# Towtank_manual_direction.net
KiCad netlist of a schematic drawn in EAGLE
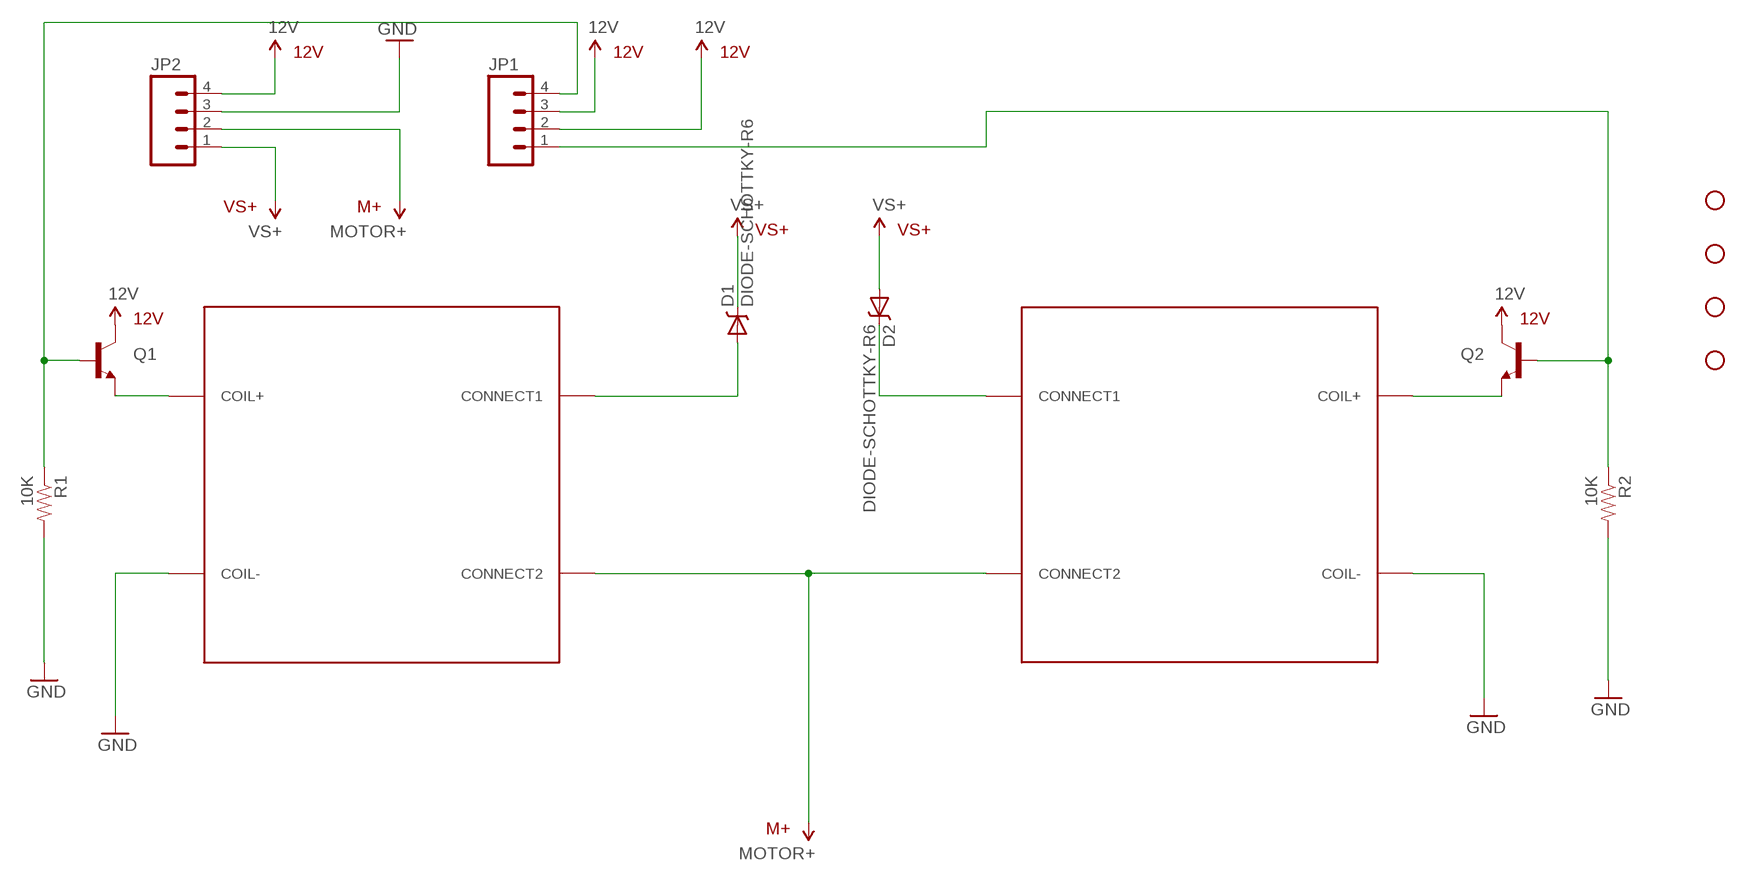
[diagram p0: schematic, sheet 1]

(export (version "E")
  (design (tool "Eeschema 10.0.6"))
  (components
    (comp (ref "D1")
      (value "DIODE-SCHOTTKY-R6")
      (footprint "eagle-import:R6-AXIAL")
      (libsource (lib "eagle-import") (part "DIODE-SCHOTTKY-R6"))
    )
    (comp (ref "D2")
      (value "DIODE-SCHOTTKY-R6")
      (footprint "eagle-import:R6-AXIAL")
      (libsource (lib "eagle-import") (part "DIODE-SCHOTTKY-R6"))
    )
    (comp (ref "JP1")
      (value "M04LOCK_LONGPADS")
      (footprint "eagle-import:1X04_LOCK_LONGPADS")
      (libsource (lib "eagle-import") (part "M04LOCK_LONGPADS"))
    )
    (comp (ref "JP2")
      (value "M04SCREW_LOCK")
      (footprint "eagle-import:SCREWTERMINAL-3.5MM-4_LOCK")
      (libsource (lib "eagle-import") (part "M04SCREW_LOCK"))
    )
    (comp (ref "JP3")
      (value "STAND-OFF")
      (footprint "eagle-import:STAND-OFF")
      (libsource (lib "eagle-import") (part "STAND-OFF"))
    )
    (comp (ref "JP4")
      (value "STAND-OFF")
      (footprint "eagle-import:STAND-OFF")
      (libsource (lib "eagle-import") (part "STAND-OFF"))
    )
    (comp (ref "JP5")
      (value "STAND-OFF")
      (footprint "eagle-import:STAND-OFF")
      (libsource (lib "eagle-import") (part "STAND-OFF"))
    )
    (comp (ref "JP6")
      (value "STAND-OFF")
      (footprint "eagle-import:STAND-OFF")
      (libsource (lib "eagle-import") (part "STAND-OFF"))
    )
    (comp (ref "Q1")
      (value "TRANSISTOR_NPNTO-92-AMMO")
      (footprint "eagle-import:TO-92-AMMO")
      (libsource (lib "eagle-import") (part "TRANSISTOR_NPNTO-92-AMMO"))
    )
    (comp (ref "Q2")
      (value "TRANSISTOR_NPNTO-92-AMMO")
      (footprint "eagle-import:TO-92-AMMO")
      (libsource (lib "eagle-import") (part "TRANSISTOR_NPNTO-92-AMMO"))
    )
    (comp (ref "R1")
      (value "10K")
      (footprint "eagle-import:AXIAL-0.4")
      (libsource (lib "eagle-import") (part "RESISTORPTH-1/4W"))
    )
    (comp (ref "R2")
      (value "10K")
      (footprint "eagle-import:AXIAL-0.4")
      (libsource (lib "eagle-import") (part "RESISTORPTH-1/4W"))
    )
    (comp (ref "U1")
      (value "G5LE-1A4_SPST-NO")
      (footprint "eagle-import:PC-PIN")
      (libsource (lib "eagle-import") (part "G5LE-1A4_SPST-NO"))
    )
    (comp (ref "U2")
      (value "G5LE-1A4_SPST-NO")
      (footprint "eagle-import:PC-PIN")
      (libsource (lib "eagle-import") (part "G5LE-1A4_SPST-NO"))
    )
  )
  (nets
    (net (code "1") (name "12V") (class "Default")
      (node (ref "JP1") (pin "2") (pinfunction "2_2") (pintype "passive"))
      (node (ref "JP1") (pin "3") (pinfunction "3_3") (pintype "passive"))
      (node (ref "JP2") (pin "4") (pinfunction "4_4") (pintype "passive"))
      (node (ref "Q1") (pin "3") (pinfunction "C_3") (pintype "passive"))
      (node (ref "Q2") (pin "3") (pinfunction "C_3") (pintype "passive"))
    )
    (net (code "2") (name "GND") (class "Default")
      (node (ref "JP2") (pin "3") (pinfunction "3_3") (pintype "passive"))
      (node (ref "R1") (pin "P$2") (pinfunction "2_P$2") (pintype "passive"))
      (node (ref "R2") (pin "P$2") (pinfunction "2_P$2") (pintype "passive"))
      (node (ref "U1") (pin "COIL-") (pinfunction "COIL-_COIL-") (pintype "bidirectional"))
      (node (ref "U2") (pin "COIL-") (pinfunction "COIL-_COIL-") (pintype "bidirectional"))
    )
    (net (code "3") (name "MOTOR+") (class "Default")
      (node (ref "JP2") (pin "2") (pinfunction "2_2") (pintype "passive"))
      (node (ref "U1") (pin "CONNECT2") (pinfunction "CONNECT2_CONNECT2") (pintype "bidirectional"))
      (node (ref "U2") (pin "CONNECT2") (pinfunction "CONNECT2_CONNECT2") (pintype "bidirectional"))
    )
    (net (code "4") (name "Net-(D1-ANODE)") (class "Default")
      (node (ref "D1") (pin "P$ANODE") (pinfunction "ANODE_P$ANODE") (pintype "passive"))
      (node (ref "U1") (pin "CONNECT1") (pinfunction "CONNECT1_CONNECT1") (pintype "bidirectional"))
    )
    (net (code "5") (name "Net-(D2-CATHODE)") (class "Default")
      (node (ref "D2") (pin "P$CATHODE") (pinfunction "CATHODE_P$CATHODE") (pintype "passive"))
      (node (ref "U2") (pin "CONNECT1") (pinfunction "CONNECT1_CONNECT1") (pintype "bidirectional"))
    )
    (net (code "6") (name "Net-(Q1-B)") (class "Default")
      (node (ref "JP1") (pin "4") (pinfunction "4_4") (pintype "passive"))
      (node (ref "Q1") (pin "2") (pinfunction "B_2") (pintype "passive"))
      (node (ref "R1") (pin "P$1") (pinfunction "1_P$1") (pintype "passive"))
    )
    (net (code "7") (name "Net-(Q1-E)") (class "Default")
      (node (ref "Q1") (pin "1") (pinfunction "E_1") (pintype "passive"))
      (node (ref "U1") (pin "COIL+") (pinfunction "COIL+_COIL+") (pintype "bidirectional"))
    )
    (net (code "8") (name "Net-(Q2-B)") (class "Default")
      (node (ref "JP1") (pin "1") (pinfunction "1_1") (pintype "passive"))
      (node (ref "Q2") (pin "2") (pinfunction "B_2") (pintype "passive"))
      (node (ref "R2") (pin "P$1") (pinfunction "1_P$1") (pintype "passive"))
    )
    (net (code "9") (name "Net-(Q2-E)") (class "Default")
      (node (ref "Q2") (pin "1") (pinfunction "E_1") (pintype "passive"))
      (node (ref "U2") (pin "COIL+") (pinfunction "COIL+_COIL+") (pintype "bidirectional"))
    )
    (net (code "10") (name "VS+") (class "Default")
      (node (ref "D1") (pin "P$CATHODE") (pinfunction "CATHODE_P$CATHODE") (pintype "passive"))
      (node (ref "D2") (pin "P$ANODE") (pinfunction "ANODE_P$ANODE") (pintype "passive"))
      (node (ref "JP2") (pin "1") (pinfunction "1_1") (pintype "passive"))
    )
  )
)
